# caretaker-remotecontrol.net
KiCad netlist of a schematic drawn in EAGLE
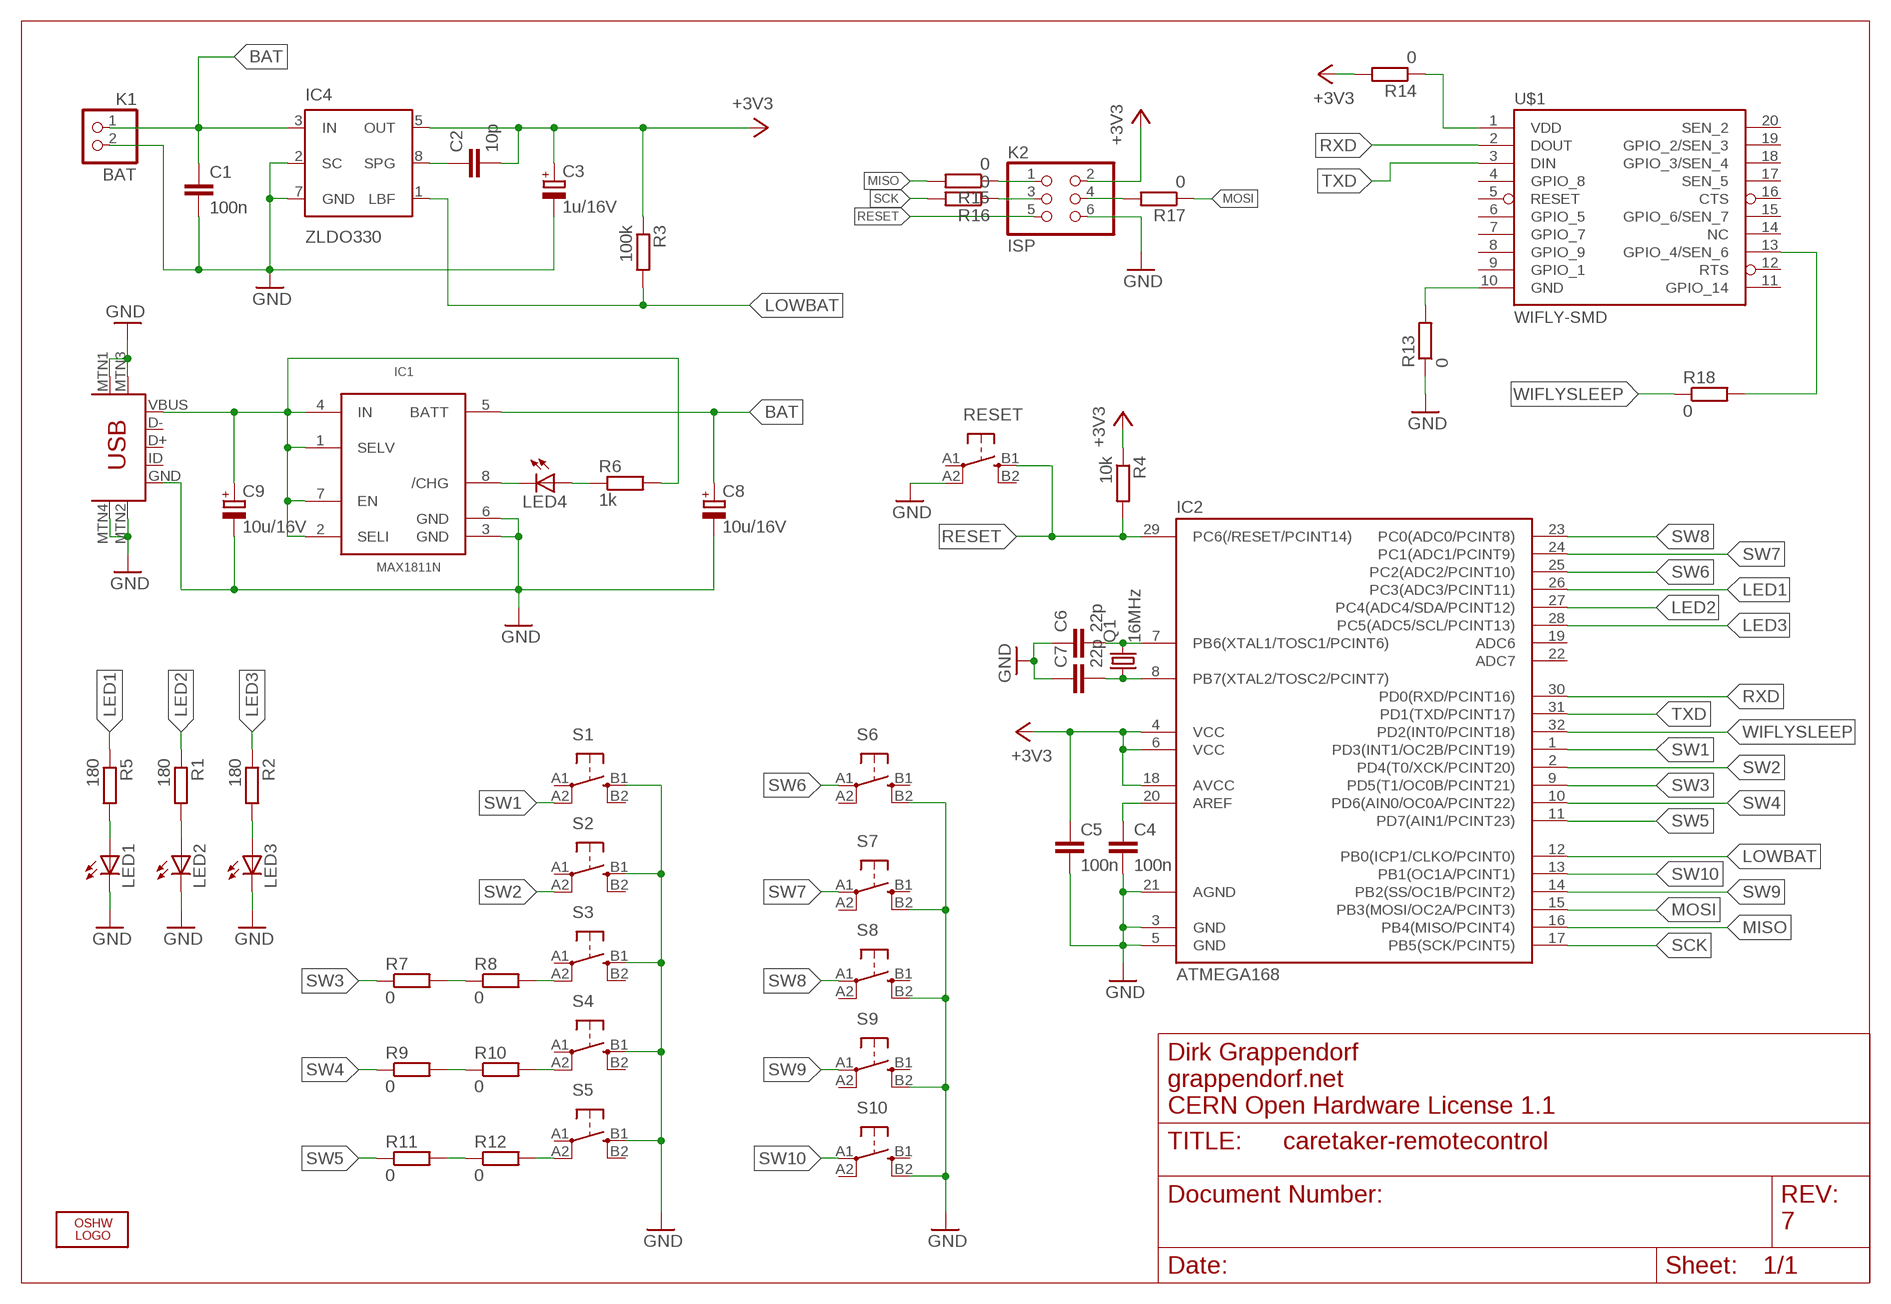
[diagram p0: schematic, sheet 1]

(export (version "E")
  (design (tool "Eeschema 10.0.6"))
  (components
    (comp (ref "C1")
      (value "100n")
      (footprint "eagle-import:C1206")
      (libsource (lib "eagle-import") (part "C-EUC1206"))
    )
    (comp (ref "C2")
      (value "10p")
      (footprint "eagle-import:C1206")
      (libsource (lib "eagle-import") (part "C-EUC1206"))
    )
    (comp (ref "C3")
      (value "1u/16V")
      (footprint "eagle-import:PANASONIC_B")
      (libsource (lib "eagle-import") (part "CPOL-EUB"))
    )
    (comp (ref "C4")
      (value "100n")
      (footprint "eagle-import:C1206")
      (libsource (lib "eagle-import") (part "C-EUC1206"))
    )
    (comp (ref "C5")
      (value "100n")
      (footprint "eagle-import:C1206")
      (libsource (lib "eagle-import") (part "C-EUC1206"))
    )
    (comp (ref "C6")
      (value "22p")
      (footprint "eagle-import:C1206")
      (libsource (lib "eagle-import") (part "C-EUC1206"))
    )
    (comp (ref "C7")
      (value "22p")
      (footprint "eagle-import:C1206")
      (libsource (lib "eagle-import") (part "C-EUC1206"))
    )
    (comp (ref "C8")
      (value "10u/16V")
      (footprint "eagle-import:PANASONIC_B")
      (libsource (lib "eagle-import") (part "CPOL-EUB"))
    )
    (comp (ref "C9")
      (value "10u/16V")
      (footprint "eagle-import:PANASONIC_B")
      (libsource (lib "eagle-import") (part "CPOL-EUB"))
    )
    (comp (ref "IC1")
      (value "MAX1811N")
      (footprint "eagle-import:SO08")
      (libsource (lib "eagle-import") (part "MAX1811N"))
    )
    (comp (ref "IC2")
      (value "ATMEGA168")
      (footprint "eagle-import:TQFP32-08")
      (libsource (lib "eagle-import") (part "ATMEGA48/88/168-AU"))
    )
    (comp (ref "IC4")
      (value "ZLDO330")
      (footprint "eagle-import:SM8")
      (libsource (lib "eagle-import") (part "ZLDO330"))
    )
    (comp (ref "K1")
      (value "BAT")
      (footprint "eagle-import:1X02")
      (libsource (lib "eagle-import") (part "PINHD-1X2"))
    )
    (comp (ref "K2")
      (value "ISP")
      (footprint "eagle-import:2X03_90")
      (libsource (lib "eagle-import") (part "PINHD-2X3/90"))
    )
    (comp (ref "K3")
      (value "USB-MINIB-5PIN")
      (footprint "eagle-import:USB-MINIB")
      (libsource (lib "eagle-import") (part "USB-MINIB-5PIN"))
    )
    (comp (ref "LED1")
      (value "LEDKA-3528ASYC")
      (footprint "eagle-import:KA-3528ASYC")
      (libsource (lib "eagle-import") (part "LEDKA-3528ASYC"))
    )
    (comp (ref "LED2")
      (value "LEDKA-3528ASYC")
      (footprint "eagle-import:KA-3528ASYC")
      (libsource (lib "eagle-import") (part "LEDKA-3528ASYC"))
    )
    (comp (ref "LED3")
      (value "LEDKA-3528ASYC")
      (footprint "eagle-import:KA-3528ASYC")
      (libsource (lib "eagle-import") (part "LEDKA-3528ASYC"))
    )
    (comp (ref "LED4")
      (value "LEDKA-3528ASYC")
      (footprint "eagle-import:KA-3528ASYC")
      (libsource (lib "eagle-import") (part "LEDKA-3528ASYC"))
    )
    (comp (ref "LOGO1")
      (value "OSHW_LOGO_10MILX0350-NT")
      (footprint "eagle-import:OSHW_10X350_NOTEXT")
      (libsource (lib "eagle-import") (part "OSHW_LOGO_10MILX0350-NT"))
    )
    (comp (ref "Q1")
      (value "16MHz")
      (footprint "eagle-import:HC49UP")
      (libsource (lib "eagle-import") (part "CRYSTALHC49UP"))
    )
    (comp (ref "R1")
      (value "180")
      (footprint "eagle-import:R1206")
      (libsource (lib "eagle-import") (part "R-EU_R1206"))
    )
    (comp (ref "R2")
      (value "180")
      (footprint "eagle-import:R1206")
      (libsource (lib "eagle-import") (part "R-EU_R1206"))
    )
    (comp (ref "R3")
      (value "100k")
      (footprint "eagle-import:R1206")
      (libsource (lib "eagle-import") (part "R-EU_R1206"))
    )
    (comp (ref "R4")
      (value "10k")
      (footprint "eagle-import:R1206")
      (libsource (lib "eagle-import") (part "R-EU_R1206"))
    )
    (comp (ref "R5")
      (value "180")
      (footprint "eagle-import:R1206")
      (libsource (lib "eagle-import") (part "R-EU_R1206"))
    )
    (comp (ref "R6")
      (value "1k")
      (footprint "eagle-import:R1206")
      (libsource (lib "eagle-import") (part "R-EU_R1206"))
    )
    (comp (ref "R7")
      (value "0")
      (footprint "eagle-import:R1206")
      (libsource (lib "eagle-import") (part "R-EU_R1206"))
    )
    (comp (ref "R8")
      (value "0")
      (footprint "eagle-import:R1206")
      (libsource (lib "eagle-import") (part "R-EU_R1206"))
    )
    (comp (ref "R9")
      (value "0")
      (footprint "eagle-import:R1206")
      (libsource (lib "eagle-import") (part "R-EU_R1206"))
    )
    (comp (ref "R10")
      (value "0")
      (footprint "eagle-import:R1206")
      (libsource (lib "eagle-import") (part "R-EU_R1206"))
    )
    (comp (ref "R11")
      (value "0")
      (footprint "eagle-import:R1206")
      (libsource (lib "eagle-import") (part "R-EU_R1206"))
    )
    (comp (ref "R12")
      (value "0")
      (footprint "eagle-import:R1206")
      (libsource (lib "eagle-import") (part "R-EU_R1206"))
    )
    (comp (ref "R13")
      (value "0")
      (footprint "eagle-import:R1206")
      (libsource (lib "eagle-import") (part "R-EU_R1206"))
    )
    (comp (ref "R14")
      (value "0")
      (footprint "eagle-import:R1206")
      (libsource (lib "eagle-import") (part "R-EU_R1206"))
    )
    (comp (ref "R15")
      (value "0")
      (footprint "eagle-import:R1206")
      (libsource (lib "eagle-import") (part "R-EU_R1206"))
    )
    (comp (ref "R16")
      (value "0")
      (footprint "eagle-import:R1206")
      (libsource (lib "eagle-import") (part "R-EU_R1206"))
    )
    (comp (ref "R17")
      (value "0")
      (footprint "eagle-import:R1206")
      (libsource (lib "eagle-import") (part "R-EU_R1206"))
    )
    (comp (ref "R18")
      (value "0")
      (footprint "eagle-import:R1206")
      (libsource (lib "eagle-import") (part "R-EU_R1206"))
    )
    (comp (ref "RESET")
      (value "TAC_SWITCHSMD-BIG")
      (footprint "eagle-import:TACTILE_SWITCH_TALL")
      (libsource (lib "eagle-import") (part "TAC_SWITCHSMD-BIG"))
    )
    (comp (ref "S1")
      (value "TAC_SWITCHSMD-BIG")
      (footprint "eagle-import:TACTILE_SWITCH_TALL")
      (libsource (lib "eagle-import") (part "TAC_SWITCHSMD-BIG"))
    )
    (comp (ref "S2")
      (value "TAC_SWITCHSMD-BIG")
      (footprint "eagle-import:TACTILE_SWITCH_TALL")
      (libsource (lib "eagle-import") (part "TAC_SWITCHSMD-BIG"))
    )
    (comp (ref "S3")
      (value "TAC_SWITCHSMD-BIG")
      (footprint "eagle-import:TACTILE_SWITCH_TALL")
      (libsource (lib "eagle-import") (part "TAC_SWITCHSMD-BIG"))
    )
    (comp (ref "S4")
      (value "TAC_SWITCHSMD-BIG")
      (footprint "eagle-import:TACTILE_SWITCH_TALL")
      (libsource (lib "eagle-import") (part "TAC_SWITCHSMD-BIG"))
    )
    (comp (ref "S5")
      (value "TAC_SWITCHSMD-BIG")
      (footprint "eagle-import:TACTILE_SWITCH_TALL")
      (libsource (lib "eagle-import") (part "TAC_SWITCHSMD-BIG"))
    )
    (comp (ref "S6")
      (value "TAC_SWITCHSMD-BIG")
      (footprint "eagle-import:TACTILE_SWITCH_TALL")
      (libsource (lib "eagle-import") (part "TAC_SWITCHSMD-BIG"))
    )
    (comp (ref "S7")
      (value "TAC_SWITCHSMD-BIG")
      (footprint "eagle-import:TACTILE_SWITCH_TALL")
      (libsource (lib "eagle-import") (part "TAC_SWITCHSMD-BIG"))
    )
    (comp (ref "S8")
      (value "TAC_SWITCHSMD-BIG")
      (footprint "eagle-import:TACTILE_SWITCH_TALL")
      (libsource (lib "eagle-import") (part "TAC_SWITCHSMD-BIG"))
    )
    (comp (ref "S9")
      (value "TAC_SWITCHSMD-BIG")
      (footprint "eagle-import:TACTILE_SWITCH_TALL")
      (libsource (lib "eagle-import") (part "TAC_SWITCHSMD-BIG"))
    )
    (comp (ref "S10")
      (value "TAC_SWITCHSMD-BIG")
      (footprint "eagle-import:TACTILE_SWITCH_TALL")
      (libsource (lib "eagle-import") (part "TAC_SWITCHSMD-BIG"))
    )
    (comp (ref "U$1")
      (value "WIFLY-SMD")
      (footprint "eagle-import:WIFLY-SMD")
      (libsource (lib "eagle-import") (part "WIFLY-SMD"))
    )
  )
  (nets
    (net (code "1") (name "+3V3") (class "Default")
      (node (ref "C2") (pin "2") (pinfunction "2_2") (pintype "passive"))
      (node (ref "C3") (pin "+") (pinfunction "+_+") (pintype "passive"))
      (node (ref "C5") (pin "1") (pinfunction "1_1") (pintype "passive"))
      (node (ref "IC2") (pin "18") (pinfunction "AVCC_18") (pintype "passive"))
      (node (ref "IC2") (pin "4") (pinfunction "VCC_4") (pintype "power_in"))
      (node (ref "IC2") (pin "6") (pinfunction "VCC_6") (pintype "power_in"))
      (node (ref "IC4") (pin "5") (pinfunction "OUT_5") (pintype "output"))
      (node (ref "K2") (pin "2") (pinfunction "2_2") (pintype "passive"))
      (node (ref "R14") (pin "2") (pinfunction "2_2") (pintype "passive"))
      (node (ref "R3") (pin "1") (pinfunction "1_1") (pintype "passive"))
      (node (ref "R4") (pin "1") (pinfunction "1_1") (pintype "passive"))
    )
    (net (code "2") (name "BAT") (class "Default")
      (node (ref "C1") (pin "1") (pinfunction "1_1") (pintype "passive"))
      (node (ref "C8") (pin "+") (pinfunction "+_+") (pintype "passive"))
      (node (ref "IC1") (pin "5") (pinfunction "BATT_5") (pintype "bidirectional"))
      (node (ref "IC4") (pin "3") (pinfunction "IN_3") (pintype "input"))
      (node (ref "K1") (pin "1") (pinfunction "1_1") (pintype "passive"))
    )
    (net (code "3") (name "GND") (class "Default")
      (node (ref "C1") (pin "2") (pinfunction "2_2") (pintype "passive"))
      (node (ref "C3") (pin "-") (pinfunction "-_-") (pintype "passive"))
      (node (ref "C4") (pin "2") (pinfunction "2_2") (pintype "passive"))
      (node (ref "C5") (pin "2") (pinfunction "2_2") (pintype "passive"))
      (node (ref "C6") (pin "1") (pinfunction "1_1") (pintype "passive"))
      (node (ref "C7") (pin "1") (pinfunction "1_1") (pintype "passive"))
      (node (ref "C8") (pin "-") (pinfunction "-_-") (pintype "passive"))
      (node (ref "C9") (pin "-") (pinfunction "-_-") (pintype "passive"))
      (node (ref "IC1") (pin "3") (pinfunction "GND_3") (pintype "bidirectional"))
      (node (ref "IC1") (pin "6") (pinfunction "GND_6") (pintype "bidirectional"))
      (node (ref "IC2") (pin "21") (pinfunction "AGND_21") (pintype "power_in"))
      (node (ref "IC2") (pin "3") (pinfunction "GND_3") (pintype "power_in"))
      (node (ref "IC2") (pin "5") (pinfunction "GND_5") (pintype "power_in"))
      (node (ref "IC4") (pin "2") (pinfunction "SC_2") (pintype "input"))
      (node (ref "IC4") (pin "7") (pinfunction "GND_7") (pintype "power_in"))
      (node (ref "K1") (pin "2") (pinfunction "2_2") (pintype "passive"))
      (node (ref "K2") (pin "6") (pinfunction "6_6") (pintype "passive"))
      (node (ref "K3") (pin "GND") (pinfunction "GND_GND") (pintype "bidirectional"))
      (node (ref "K3") (pin "MTN1") (pinfunction "MTN2_MTN1") (pintype "bidirectional"))
      (node (ref "K3") (pin "MTN2") (pinfunction "MTN3_MTN2") (pintype "bidirectional"))
      (node (ref "K3") (pin "MTN3") (pinfunction "MTN1_MTN3") (pintype "bidirectional"))
      (node (ref "K3") (pin "MTN4") (pinfunction "MTN4_MTN4") (pintype "bidirectional"))
      (node (ref "LED1") (pin "C") (pinfunction "C_C") (pintype "passive"))
      (node (ref "LED2") (pin "C") (pinfunction "C_C") (pintype "passive"))
      (node (ref "LED3") (pin "C") (pinfunction "C_C") (pintype "passive"))
      (node (ref "R13") (pin "1") (pinfunction "1_1") (pintype "passive"))
      (node (ref "RESET") (pin "A2") (pinfunction "2_A2") (pintype "passive"))
      (node (ref "S1") (pin "B1") (pinfunction "3_B1") (pintype "passive"))
      (node (ref "S10") (pin "B2") (pinfunction "4_B2") (pintype "passive"))
      (node (ref "S2") (pin "B1") (pinfunction "3_B1") (pintype "passive"))
      (node (ref "S3") (pin "B1") (pinfunction "3_B1") (pintype "passive"))
      (node (ref "S4") (pin "B1") (pinfunction "3_B1") (pintype "passive"))
      (node (ref "S5") (pin "B1") (pinfunction "3_B1") (pintype "passive"))
      (node (ref "S6") (pin "B2") (pinfunction "4_B2") (pintype "passive"))
      (node (ref "S7") (pin "B2") (pinfunction "4_B2") (pintype "passive"))
      (node (ref "S8") (pin "B2") (pinfunction "4_B2") (pintype "passive"))
      (node (ref "S9") (pin "B2") (pinfunction "4_B2") (pintype "passive"))
    )
    (net (code "4") (name "LED1") (class "Default")
      (node (ref "IC2") (pin "26") (pinfunction "PC3(ADC3/PCINT11)_26") (pintype "bidirectional"))
      (node (ref "R5") (pin "1") (pinfunction "1_1") (pintype "passive"))
    )
    (net (code "5") (name "LED2") (class "Default")
      (node (ref "IC2") (pin "27") (pinfunction "PC4(ADC4/SDA/PCINT12)_27") (pintype "bidirectional"))
      (node (ref "R1") (pin "1") (pinfunction "1_1") (pintype "passive"))
    )
    (net (code "6") (name "LED3") (class "Default")
      (node (ref "IC2") (pin "28") (pinfunction "PC5(ADC5/SCL/PCINT13)_28") (pintype "bidirectional"))
      (node (ref "R2") (pin "1") (pinfunction "1_1") (pintype "passive"))
    )
    (net (code "7") (name "LOWBAT") (class "Default")
      (node (ref "IC2") (pin "12") (pinfunction "PB0(ICP1/CLKO/PCINT0)_12") (pintype "bidirectional"))
      (node (ref "IC4") (pin "1") (pinfunction "LBF_1") (pintype "output"))
      (node (ref "R3") (pin "2") (pinfunction "2_2") (pintype "passive"))
    )
    (net (code "8") (name "MISO") (class "Default")
      (node (ref "IC2") (pin "16") (pinfunction "PB4(MISO/PCINT4)_16") (pintype "bidirectional"))
      (node (ref "R15") (pin "2") (pinfunction "2_2") (pintype "passive"))
    )
    (net (code "9") (name "MOSI") (class "Default")
      (node (ref "IC2") (pin "15") (pinfunction "PB3(MOSI/OC2A/PCINT3)_15") (pintype "bidirectional"))
      (node (ref "R17") (pin "1") (pinfunction "1_1") (pintype "passive"))
    )
    (net (code "10") (name "Net-(IC1-EN)") (class "Default")
      (node (ref "C9") (pin "+") (pinfunction "+_+") (pintype "passive"))
      (node (ref "IC1") (pin "1") (pinfunction "SELV_1") (pintype "bidirectional"))
      (node (ref "IC1") (pin "2") (pinfunction "SELI_2") (pintype "bidirectional"))
      (node (ref "IC1") (pin "4") (pinfunction "IN_4") (pintype "bidirectional"))
      (node (ref "IC1") (pin "7") (pinfunction "EN_7") (pintype "bidirectional"))
      (node (ref "K3") (pin "VBUS") (pinfunction "VBUS_VBUS") (pintype "bidirectional"))
      (node (ref "R6") (pin "2") (pinfunction "2_2") (pintype "passive"))
    )
    (net (code "11") (name "Net-(IC1-{slash}CHG)") (class "Default")
      (node (ref "IC1") (pin "8") (pinfunction "/CHG_8") (pintype "bidirectional"))
      (node (ref "LED4") (pin "C") (pinfunction "C_C") (pintype "passive"))
    )
    (net (code "12") (name "Net-(IC2-AREF)") (class "Default")
      (node (ref "C4") (pin "1") (pinfunction "1_1") (pintype "passive"))
      (node (ref "IC2") (pin "20") (pinfunction "AREF_20") (pintype "passive"))
    )
    (net (code "13") (name "Net-(IC2-PB6(XTAL1{slash}TOSC1{slash}PCINT6))") (class "Default")
      (node (ref "C6") (pin "2") (pinfunction "2_2") (pintype "passive"))
      (node (ref "IC2") (pin "7") (pinfunction "PB6(XTAL1/TOSC1/PCINT6)_7") (pintype "bidirectional"))
      (node (ref "Q1") (pin "2") (pinfunction "2_2") (pintype "passive"))
    )
    (net (code "14") (name "Net-(IC2-PB7(XTAL2{slash}TOSC2{slash}PCINT7))") (class "Default")
      (node (ref "C7") (pin "2") (pinfunction "2_2") (pintype "passive"))
      (node (ref "IC2") (pin "8") (pinfunction "PB7(XTAL2/TOSC2/PCINT7)_8") (pintype "bidirectional"))
      (node (ref "Q1") (pin "1") (pinfunction "1_1") (pintype "passive"))
    )
    (net (code "15") (name "Net-(IC4-SPG)") (class "Default")
      (node (ref "C2") (pin "1") (pinfunction "1_1") (pintype "passive"))
      (node (ref "IC4") (pin "8") (pinfunction "SPG_8") (pintype "input"))
    )
    (net (code "16") (name "Net-(K2-Pad1)") (class "Default")
      (node (ref "K2") (pin "1") (pinfunction "1_1") (pintype "passive"))
      (node (ref "R15") (pin "1") (pinfunction "1_1") (pintype "passive"))
    )
    (net (code "17") (name "Net-(K2-Pad3)") (class "Default")
      (node (ref "K2") (pin "3") (pinfunction "3_3") (pintype "passive"))
      (node (ref "R16") (pin "1") (pinfunction "1_1") (pintype "passive"))
    )
    (net (code "18") (name "Net-(K2-Pad4)") (class "Default")
      (node (ref "K2") (pin "4") (pinfunction "4_4") (pintype "passive"))
      (node (ref "R17") (pin "2") (pinfunction "2_2") (pintype "passive"))
    )
    (net (code "19") (name "Net-(LED1-PadA)") (class "Default")
      (node (ref "LED1") (pin "A") (pinfunction "A_A") (pintype "passive"))
      (node (ref "R5") (pin "2") (pinfunction "2_2") (pintype "passive"))
    )
    (net (code "20") (name "Net-(LED2-PadA)") (class "Default")
      (node (ref "LED2") (pin "A") (pinfunction "A_A") (pintype "passive"))
      (node (ref "R1") (pin "2") (pinfunction "2_2") (pintype "passive"))
    )
    (net (code "21") (name "Net-(LED3-PadA)") (class "Default")
      (node (ref "LED3") (pin "A") (pinfunction "A_A") (pintype "passive"))
      (node (ref "R2") (pin "2") (pinfunction "2_2") (pintype "passive"))
    )
    (net (code "22") (name "Net-(LED4-PadA)") (class "Default")
      (node (ref "LED4") (pin "A") (pinfunction "A_A") (pintype "passive"))
      (node (ref "R6") (pin "1") (pinfunction "1_1") (pintype "passive"))
    )
    (net (code "23") (name "Net-(R7-Pad2)") (class "Default")
      (node (ref "R7") (pin "2") (pinfunction "2_2") (pintype "passive"))
      (node (ref "R8") (pin "1") (pinfunction "1_1") (pintype "passive"))
    )
    (net (code "24") (name "Net-(R10-Pad1)") (class "Default")
      (node (ref "R10") (pin "1") (pinfunction "1_1") (pintype "passive"))
      (node (ref "R9") (pin "2") (pinfunction "2_2") (pintype "passive"))
    )
    (net (code "25") (name "Net-(R11-Pad2)") (class "Default")
      (node (ref "R11") (pin "2") (pinfunction "2_2") (pintype "passive"))
      (node (ref "R12") (pin "1") (pinfunction "1_1") (pintype "passive"))
    )
    (net (code "26") (name "Net-(S3-2)") (class "Default")
      (node (ref "R8") (pin "2") (pinfunction "2_2") (pintype "passive"))
      (node (ref "S3") (pin "A2") (pinfunction "2_A2") (pintype "passive"))
    )
    (net (code "27") (name "Net-(S4-2)") (class "Default")
      (node (ref "R10") (pin "2") (pinfunction "2_2") (pintype "passive"))
      (node (ref "S4") (pin "A2") (pinfunction "2_A2") (pintype "passive"))
    )
    (net (code "28") (name "Net-(S5-2)") (class "Default")
      (node (ref "R12") (pin "2") (pinfunction "2_2") (pintype "passive"))
      (node (ref "S5") (pin "A2") (pinfunction "2_A2") (pintype "passive"))
    )
    (net (code "29") (name "Net-(U$1-GND)") (class "Default")
      (node (ref "R13") (pin "2") (pinfunction "2_2") (pintype "passive"))
      (node (ref "U$1") (pin "10") (pinfunction "GND_10") (pintype "power_in"))
    )
    (net (code "30") (name "Net-(U$1-GPIO_4{slash}SEN_6)") (class "Default")
      (node (ref "R18") (pin "2") (pinfunction "2_2") (pintype "passive"))
      (node (ref "U$1") (pin "13") (pinfunction "GPIO_4/SEN_6_13") (pintype "bidirectional"))
    )
    (net (code "31") (name "Net-(U$1-VDD)") (class "Default")
      (node (ref "R14") (pin "1") (pinfunction "1_1") (pintype "passive"))
      (node (ref "U$1") (pin "1") (pinfunction "VDD_1") (pintype "power_in"))
    )
    (net (code "32") (name "RESET") (class "Default")
      (node (ref "IC2") (pin "29") (pinfunction "PC6(/RESET/PCINT14)_29") (pintype "bidirectional"))
      (node (ref "K2") (pin "5") (pinfunction "5_5") (pintype "passive"))
      (node (ref "R4") (pin "2") (pinfunction "2_2") (pintype "passive"))
      (node (ref "RESET") (pin "B1") (pinfunction "3_B1") (pintype "passive"))
    )
    (net (code "33") (name "RXD") (class "Default")
      (node (ref "IC2") (pin "30") (pinfunction "PD0(RXD/PCINT16)_30") (pintype "bidirectional"))
      (node (ref "U$1") (pin "2") (pinfunction "DOUT_2") (pintype "output"))
    )
    (net (code "34") (name "SCK") (class "Default")
      (node (ref "IC2") (pin "17") (pinfunction "PB5(SCK/PCINT5)_17") (pintype "bidirectional"))
      (node (ref "R16") (pin "2") (pinfunction "2_2") (pintype "passive"))
    )
    (net (code "35") (name "SW1") (class "Default")
      (node (ref "IC2") (pin "1") (pinfunction "PD3(INT1/OC2B/PCINT19)_1") (pintype "bidirectional"))
      (node (ref "S1") (pin "A2") (pinfunction "2_A2") (pintype "passive"))
    )
    (net (code "36") (name "SW2") (class "Default")
      (node (ref "IC2") (pin "2") (pinfunction "PD4(T0/XCK/PCINT20)_2") (pintype "bidirectional"))
      (node (ref "S2") (pin "A2") (pinfunction "2_A2") (pintype "passive"))
    )
    (net (code "37") (name "SW3") (class "Default")
      (node (ref "IC2") (pin "9") (pinfunction "PD5(T1/OC0B/PCINT21)_9") (pintype "bidirectional"))
      (node (ref "R7") (pin "1") (pinfunction "1_1") (pintype "passive"))
    )
    (net (code "38") (name "SW4") (class "Default")
      (node (ref "IC2") (pin "10") (pinfunction "PD6(AIN0/OC0A/PCINT22)_10") (pintype "bidirectional"))
      (node (ref "R9") (pin "1") (pinfunction "1_1") (pintype "passive"))
    )
    (net (code "39") (name "SW5") (class "Default")
      (node (ref "IC2") (pin "11") (pinfunction "PD7(AIN1/PCINT23)_11") (pintype "bidirectional"))
      (node (ref "R11") (pin "1") (pinfunction "1_1") (pintype "passive"))
    )
    (net (code "40") (name "SW6") (class "Default")
      (node (ref "IC2") (pin "25") (pinfunction "PC2(ADC2/PCINT10)_25") (pintype "bidirectional"))
      (node (ref "S6") (pin "A1") (pinfunction "1_A1") (pintype "passive"))
    )
    (net (code "41") (name "SW7") (class "Default")
      (node (ref "IC2") (pin "24") (pinfunction "PC1(ADC1/PCINT9)_24") (pintype "bidirectional"))
      (node (ref "S7") (pin "A1") (pinfunction "1_A1") (pintype "passive"))
    )
    (net (code "42") (name "SW8") (class "Default")
      (node (ref "IC2") (pin "23") (pinfunction "PC0(ADC0/PCINT8)_23") (pintype "bidirectional"))
      (node (ref "S8") (pin "A1") (pinfunction "1_A1") (pintype "passive"))
    )
    (net (code "43") (name "SW9") (class "Default")
      (node (ref "IC2") (pin "14") (pinfunction "PB2(SS/OC1B/PCINT2)_14") (pintype "bidirectional"))
      (node (ref "S9") (pin "A1") (pinfunction "1_A1") (pintype "passive"))
    )
    (net (code "44") (name "SW10") (class "Default")
      (node (ref "IC2") (pin "13") (pinfunction "PB1(OC1A/PCINT1)_13") (pintype "bidirectional"))
      (node (ref "S10") (pin "A1") (pinfunction "1_A1") (pintype "passive"))
    )
    (net (code "45") (name "TXD") (class "Default")
      (node (ref "IC2") (pin "31") (pinfunction "PD1(TXD/PCINT17)_31") (pintype "bidirectional"))
      (node (ref "U$1") (pin "3") (pinfunction "DIN_3") (pintype "input"))
    )
    (net (code "46") (name "WIFLYSLEEP") (class "Default")
      (node (ref "IC2") (pin "32") (pinfunction "PD2(INT0/PCINT18)_32") (pintype "bidirectional"))
      (node (ref "R18") (pin "1") (pinfunction "1_1") (pintype "passive"))
    )
    (net (code "47") (name "unconnected-(IC2-ADC6-Pad19)") (class "Default")
      (node (ref "IC2") (pin "19") (pinfunction "ADC6_19") (pintype "passive"))
    )
    (net (code "48") (name "unconnected-(IC2-ADC7-Pad22)") (class "Default")
      (node (ref "IC2") (pin "22") (pinfunction "ADC7_22") (pintype "passive"))
    )
    (net (code "49") (name "unconnected-(K3-PadD+)") (class "Default")
      (node (ref "K3") (pin "D+") (pinfunction "D+_D+") (pintype "bidirectional"))
    )
    (net (code "50") (name "unconnected-(K3-PadD-)") (class "Default")
      (node (ref "K3") (pin "D-") (pinfunction "D-_D-") (pintype "bidirectional"))
    )
    (net (code "51") (name "unconnected-(K3-PadID)") (class "Default")
      (node (ref "K3") (pin "ID") (pinfunction "ID_ID") (pintype "bidirectional"))
    )
    (net (code "52") (name "unconnected-(RESET-1-PadA1)") (class "Default")
      (node (ref "RESET") (pin "A1") (pinfunction "1_A1") (pintype "passive"))
    )
    (net (code "53") (name "unconnected-(RESET-4-PadB2)") (class "Default")
      (node (ref "RESET") (pin "B2") (pinfunction "4_B2") (pintype "passive"))
    )
    (net (code "54") (name "unconnected-(S1-1-PadA1)") (class "Default")
      (node (ref "S1") (pin "A1") (pinfunction "1_A1") (pintype "passive"))
    )
    (net (code "55") (name "unconnected-(S1-4-PadB2)") (class "Default")
      (node (ref "S1") (pin "B2") (pinfunction "4_B2") (pintype "passive"))
    )
    (net (code "56") (name "unconnected-(S2-1-PadA1)") (class "Default")
      (node (ref "S2") (pin "A1") (pinfunction "1_A1") (pintype "passive"))
    )
    (net (code "57") (name "unconnected-(S2-4-PadB2)") (class "Default")
      (node (ref "S2") (pin "B2") (pinfunction "4_B2") (pintype "passive"))
    )
    (net (code "58") (name "unconnected-(S3-1-PadA1)") (class "Default")
      (node (ref "S3") (pin "A1") (pinfunction "1_A1") (pintype "passive"))
    )
    (net (code "59") (name "unconnected-(S3-4-PadB2)") (class "Default")
      (node (ref "S3") (pin "B2") (pinfunction "4_B2") (pintype "passive"))
    )
    (net (code "60") (name "unconnected-(S4-1-PadA1)") (class "Default")
      (node (ref "S4") (pin "A1") (pinfunction "1_A1") (pintype "passive"))
    )
    (net (code "61") (name "unconnected-(S4-4-PadB2)") (class "Default")
      (node (ref "S4") (pin "B2") (pinfunction "4_B2") (pintype "passive"))
    )
    (net (code "62") (name "unconnected-(S5-1-PadA1)") (class "Default")
      (node (ref "S5") (pin "A1") (pinfunction "1_A1") (pintype "passive"))
    )
    (net (code "63") (name "unconnected-(S5-4-PadB2)") (class "Default")
      (node (ref "S5") (pin "B2") (pinfunction "4_B2") (pintype "passive"))
    )
    (net (code "64") (name "unconnected-(S6-2-PadA2)") (class "Default")
      (node (ref "S6") (pin "A2") (pinfunction "2_A2") (pintype "passive"))
    )
    (net (code "65") (name "unconnected-(S6-3-PadB1)") (class "Default")
      (node (ref "S6") (pin "B1") (pinfunction "3_B1") (pintype "passive"))
    )
    (net (code "66") (name "unconnected-(S7-2-PadA2)") (class "Default")
      (node (ref "S7") (pin "A2") (pinfunction "2_A2") (pintype "passive"))
    )
    (net (code "67") (name "unconnected-(S7-3-PadB1)") (class "Default")
      (node (ref "S7") (pin "B1") (pinfunction "3_B1") (pintype "passive"))
    )
    (net (code "68") (name "unconnected-(S8-2-PadA2)") (class "Default")
      (node (ref "S8") (pin "A2") (pinfunction "2_A2") (pintype "passive"))
    )
    (net (code "69") (name "unconnected-(S8-3-PadB1)") (class "Default")
      (node (ref "S8") (pin "B1") (pinfunction "3_B1") (pintype "passive"))
    )
    (net (code "70") (name "unconnected-(S9-2-PadA2)") (class "Default")
      (node (ref "S9") (pin "A2") (pinfunction "2_A2") (pintype "passive"))
    )
    (net (code "71") (name "unconnected-(S9-3-PadB1)") (class "Default")
      (node (ref "S9") (pin "B1") (pinfunction "3_B1") (pintype "passive"))
    )
    (net (code "72") (name "unconnected-(S10-2-PadA2)") (class "Default")
      (node (ref "S10") (pin "A2") (pinfunction "2_A2") (pintype "passive"))
    )
    (net (code "73") (name "unconnected-(S10-3-PadB1)") (class "Default")
      (node (ref "S10") (pin "B1") (pinfunction "3_B1") (pintype "passive"))
    )
    (net (code "74") (name "unconnected-(U$1-CTS-Pad16)") (class "Default")
      (node (ref "U$1") (pin "16") (pinfunction "CTS_16") (pintype "input"))
    )
    (net (code "75") (name "unconnected-(U$1-GPIO_1-Pad9)") (class "Default")
      (node (ref "U$1") (pin "9") (pinfunction "GPIO_1_9") (pintype "bidirectional"))
    )
    (net (code "76") (name "unconnected-(U$1-GPIO_2{slash}SEN_3-Pad19)") (class "Default")
      (node (ref "U$1") (pin "19") (pinfunction "GPIO_2/SEN_3_19") (pintype "bidirectional"))
    )
    (net (code "77") (name "unconnected-(U$1-GPIO_3{slash}SEN_4-Pad18)") (class "Default")
      (node (ref "U$1") (pin "18") (pinfunction "GPIO_3/SEN_4_18") (pintype "bidirectional"))
    )
    (net (code "78") (name "unconnected-(U$1-GPIO_5-Pad6)") (class "Default")
      (node (ref "U$1") (pin "6") (pinfunction "GPIO_5_6") (pintype "bidirectional"))
    )
    (net (code "79") (name "unconnected-(U$1-GPIO_6{slash}SEN_7-Pad15)") (class "Default")
      (node (ref "U$1") (pin "15") (pinfunction "GPIO_6/SEN_7_15") (pintype "bidirectional"))
    )
    (net (code "80") (name "unconnected-(U$1-GPIO_7-Pad7)") (class "Default")
      (node (ref "U$1") (pin "7") (pinfunction "GPIO_7_7") (pintype "bidirectional"))
    )
    (net (code "81") (name "unconnected-(U$1-GPIO_8-Pad4)") (class "Default")
      (node (ref "U$1") (pin "4") (pinfunction "GPIO_8_4") (pintype "bidirectional"))
    )
    (net (code "82") (name "unconnected-(U$1-GPIO_9-Pad8)") (class "Default")
      (node (ref "U$1") (pin "8") (pinfunction "GPIO_9_8") (pintype "bidirectional"))
    )
    (net (code "83") (name "unconnected-(U$1-GPIO_14-Pad11)") (class "Default")
      (node (ref "U$1") (pin "11") (pinfunction "GPIO_14_11") (pintype "bidirectional"))
    )
    (net (code "84") (name "unconnected-(U$1-NC-Pad14)") (class "Default")
      (node (ref "U$1") (pin "14") (pinfunction "NC_14") (pintype "bidirectional"))
    )
    (net (code "85") (name "unconnected-(U$1-RESET-Pad5)") (class "Default")
      (node (ref "U$1") (pin "5") (pinfunction "RESET_5") (pintype "input"))
    )
    (net (code "86") (name "unconnected-(U$1-RTS-Pad12)") (class "Default")
      (node (ref "U$1") (pin "12") (pinfunction "RTS_12") (pintype "output"))
    )
    (net (code "87") (name "unconnected-(U$1-SEN_2-Pad20)") (class "Default")
      (node (ref "U$1") (pin "20") (pinfunction "SEN_2_20") (pintype "bidirectional"))
    )
    (net (code "88") (name "unconnected-(U$1-SEN_5-Pad17)") (class "Default")
      (node (ref "U$1") (pin "17") (pinfunction "SEN_5_17") (pintype "bidirectional"))
    )
  )
)
